# mapleCUx_large_4_1-018-not-produced.net
KiCad netlist of a schematic drawn in EAGLE
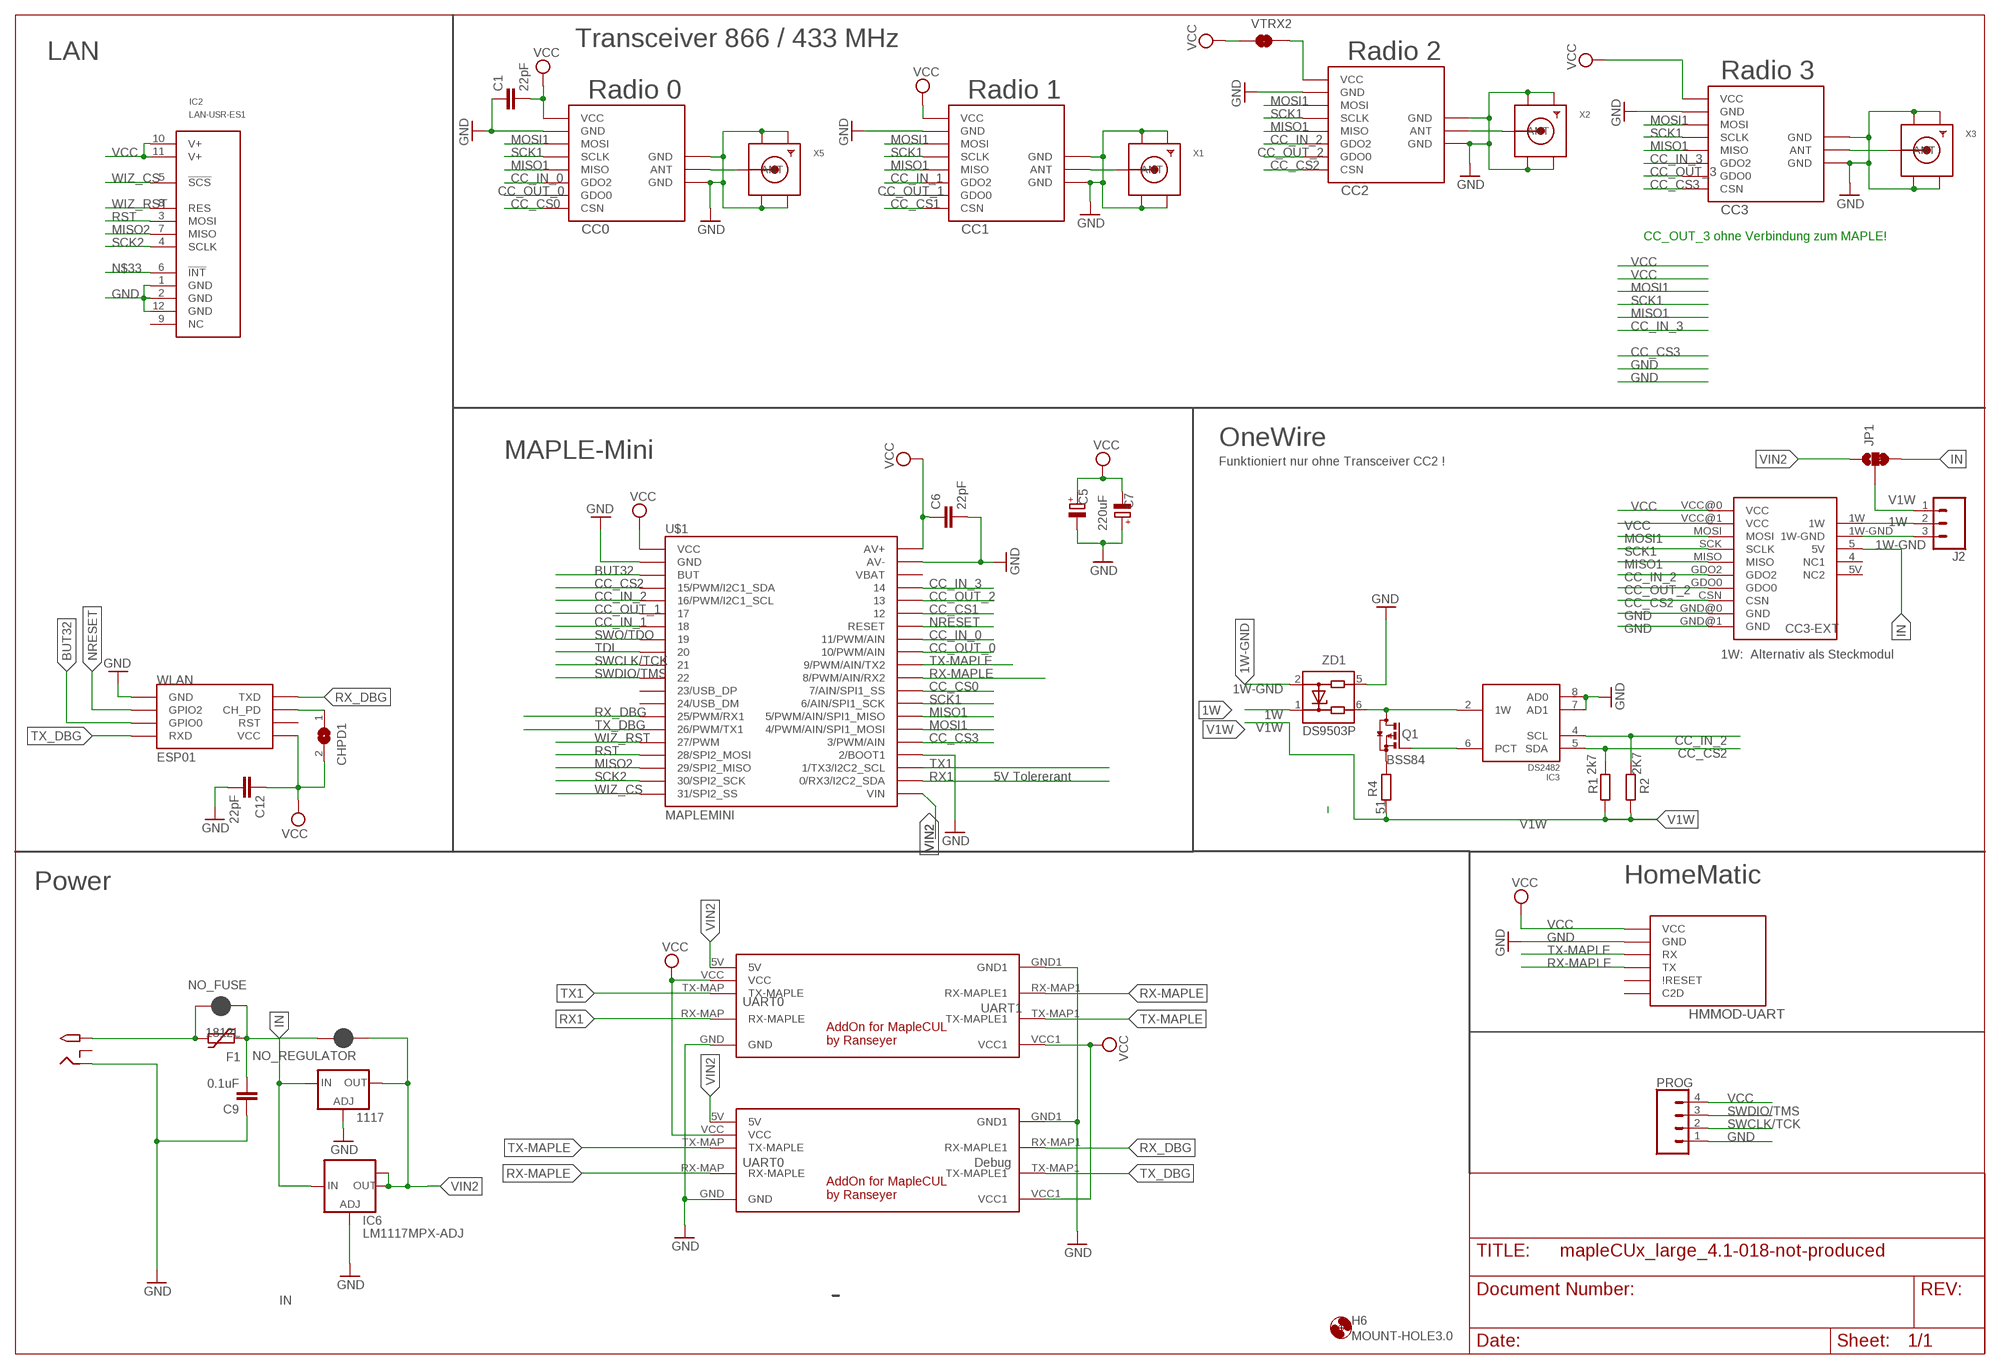
[diagram p0: schematic, sheet 1]

(export (version "E")
  (design (tool "Eeschema 10.0.6"))
  (components
    (comp (ref "1117")
      (value "LD117ADT50TR")
      (footprint "eagle-import:DPACK")
      (libsource (lib "eagle-import") (part "LD117A?DT50TR"))
    )
    (comp (ref "C1")
      (value "22pF")
      (footprint "eagle-import:C0805")
      (libsource (lib "eagle-import") (part "C-EUC0805"))
    )
    (comp (ref "C5")
      (value "220uF")
      (footprint "eagle-import:E5-8,5")
      (libsource (lib "eagle-import") (part "CPOL-EUE5-8.5"))
    )
    (comp (ref "C6")
      (value "22pF")
      (footprint "eagle-import:C0805")
      (libsource (lib "eagle-import") (part "C-EUC0805"))
    )
    (comp (ref "C7")
      (value "CPOL-EUSMCE")
      (footprint "eagle-import:SMC_E")
      (libsource (lib "eagle-import") (part "rcl_334_CPOL-EUSMCE"))
    )
    (comp (ref "C9")
      (value "0.1uF")
      (footprint "eagle-import:C1206")
      (libsource (lib "eagle-import") (part "C-EUC1206"))
    )
    (comp (ref "C12")
      (value "22pF")
      (footprint "eagle-import:C0805")
      (libsource (lib "eagle-import") (part "C-EUC0805"))
    )
    (comp (ref "CC0")
      (value "CC1101")
      (footprint "eagle-import:CC1101_MODULE1_SMD")
      (libsource (lib "eagle-import") (part "CC1101_MODULE1SMD"))
    )
    (comp (ref "CC1")
      (value "CC1101_MODULE1SMD")
      (footprint "eagle-import:CC1101_MODULE1_SMD")
      (libsource (lib "eagle-import") (part "CC1101_MODULE1SMD"))
    )
    (comp (ref "CC2")
      (value "CC1101_MODULE1SMD")
      (footprint "eagle-import:CC1101_MODULE1_SMD")
      (libsource (lib "eagle-import") (part "CC1101_MODULE1SMD"))
    )
    (comp (ref "CC3")
      (value "CC1101_MODULE1SMD")
      (footprint "eagle-import:CC1101_MODULE1_SMD")
      (libsource (lib "eagle-import") (part "CC1101_MODULE1SMD"))
    )
    (comp (ref "CC3-EXT")
      (value "ONEWIRE-MODULE")
      (footprint "eagle-import:ONEWIRE_CC1101_MODULE3_DIL")
      (libsource (lib "eagle-import") (part "ONEWIRE-MODULE"))
    )
    (comp (ref "CHPD1")
      (value "SJ")
      (footprint "eagle-import:SJ")
      (libsource (lib "eagle-import") (part "SJ"))
    )
    (comp (ref "F1")
      (value "1812L")
      (footprint "eagle-import:1812L")
      (libsource (lib "eagle-import") (part "1812L"))
    )
    (comp (ref "H6")
      (value "MOUNT-HOLE3.0")
      (footprint "eagle-import:3,0")
      (libsource (lib "eagle-import") (part "MOUNT-HOLE3.0"))
    )
    (comp (ref "HMMOD-UART")
      (value "HM-MOD-UARTDIL")
      (footprint "eagle-import:HM-MOD-UART-DIL")
      (libsource (lib "eagle-import") (part "HM-MOD-UARTDIL"))
    )
    (comp (ref "IC2")
      (value "LAN-USR-ES1")
      (footprint "eagle-import:USR-ES1")
      (libsource (lib "eagle-import") (part "LAN-USR-ES1"))
    )
    (comp (ref "IC3")
      (value "DS2482")
      (footprint "eagle-import:SO08")
      (libsource (lib "eagle-import") (part "DS2482-100S"))
    )
    (comp (ref "IC6")
      (value "LM1117MPX-ADJ")
      (footprint "eagle-import:SOT223")
      (libsource (lib "eagle-import") (part "LM1117MPX-ADJ"))
    )
    (comp (ref "J2")
      (value "CONN_03LONGPADS")
      (footprint "eagle-import:1X03_LONGPADS")
      (libsource (lib "eagle-import") (part "CONN_03LONGPADS"))
    )
    (comp (ref "JP1")
      (value "JUMPER-SMT_3_1-NC_TRACE_SILK")
      (footprint "eagle-import:SMT-JUMPER_3_1-NC_TRACE_SILK")
      (libsource (lib "eagle-import") (part "JUMPER-SMT_3_1-NC_TRACE_SILK"))
    )
    (comp (ref "NO_FUSE")
      (value "JUMPER-SMT_2_NC_PASTE_NO-SILK")
      (footprint "eagle-import:SMT-JUMPER_2_NC_PASTE_NO-SILK")
      (libsource (lib "eagle-import") (part "JUMPER-SMT_2_NC_PASTE_NO-SILK"))
    )
    (comp (ref "NO_REGULATOR")
      (value "JUMPER-SMT_2_NC_PASTE_NO-SILK")
      (footprint "eagle-import:SMT-JUMPER_2_NC_PASTE_NO-SILK")
      (libsource (lib "eagle-import") (part "JUMPER-SMT_2_NC_PASTE_NO-SILK"))
    )
    (comp (ref "PROG")
      (value "CONN_04LOCK")
      (footprint "eagle-import:1X04_LOCK")
      (libsource (lib "eagle-import") (part "CONN_04LOCK"))
    )
    (comp (ref "Q1")
      (value "BSS84")
      (footprint "eagle-import:SOT23")
      (libsource (lib "eagle-import") (part "BSS84"))
    )
    (comp (ref "R1")
      (value "2k7")
      (footprint "eagle-import:R0805")
      (libsource (lib "eagle-import") (part "R-EU_R0805"))
    )
    (comp (ref "R2")
      (value "2K7")
      (footprint "eagle-import:R0805")
      (libsource (lib "eagle-import") (part "R-EU_R0805"))
    )
    (comp (ref "R4")
      (value "51")
      (footprint "eagle-import:R0805")
      (libsource (lib "eagle-import") (part "R-EU_R0805"))
    )
    (comp (ref "U$1")
      (value "MAPLEMINI")
      (footprint "eagle-import:20-DIP")
      (libsource (lib "eagle-import") (part "MAPLEMINI"))
    )
    (comp (ref "U$2")
      (value "2.1MMJACKTHM")
      (footprint "eagle-import:PJ-102A")
      (libsource (lib "eagle-import") (part "2.1MMJACKTHM"))
    )
    (comp (ref "U$3")
      (value "MAPLE-CUL-ADDON-V01")
      (footprint "eagle-import:MAPLE-CUL-V01")
      (libsource (lib "eagle-import") (part "MAPLE-CUL-ADDON-V01"))
    )
    (comp (ref "U$4")
      (value "MAPLE-CUL-ADDON-V01")
      (footprint "eagle-import:MAPLE-CUL-V01")
      (libsource (lib "eagle-import") (part "MAPLE-CUL-ADDON-V01"))
    )
    (comp (ref "VTRX2")
      (value "JUMPER-SMT_2_NC_TRACE_SILK")
      (footprint "eagle-import:SMT-JUMPER_2_NC_TRACE_SILK")
      (libsource (lib "eagle-import") (part "JUMPER-SMT_2_NC_TRACE_SILK"))
    )
    (comp (ref "WLAN")
      (value "ESP01")
      (footprint "eagle-import:ESP01")
      (libsource (lib "eagle-import") (part "ESP01"))
    )
    (comp (ref "X1")
      (value "SMACONNECTOR_EDGE")
      (footprint "eagle-import:SMA_EDGELAUNCH")
      (libsource (lib "eagle-import") (part "SMACONNECTOR_EDGE"))
    )
    (comp (ref "X2")
      (value "SMACONNECTOR_EDGE")
      (footprint "eagle-import:SMA_EDGELAUNCH")
      (libsource (lib "eagle-import") (part "SMACONNECTOR_EDGE"))
    )
    (comp (ref "X3")
      (value "SMACONNECTOR_EDGE")
      (footprint "eagle-import:SMA_EDGELAUNCH")
      (libsource (lib "eagle-import") (part "SMACONNECTOR_EDGE"))
    )
    (comp (ref "X5")
      (value "SMACONNECTOR_EDGE")
      (footprint "eagle-import:SMA_EDGELAUNCH")
      (libsource (lib "eagle-import") (part "SMACONNECTOR_EDGE"))
    )
    (comp (ref "ZD1")
      (value "DS9503P")
      (footprint "eagle-import:TSOC6")
      (libsource (lib "eagle-import") (part "DS9503P"))
    )
  )
  (nets
    (net (code "1") (name "/CC_CS0") (class "Default")
      (node (ref "CC0") (pin "CSN") (pinfunction "CSN_CSN") (pintype "bidirectional"))
      (node (ref "U$1") (pin "29") (pinfunction "7/AIN/SPI1_SS_29") (pintype "bidirectional"))
    )
    (net (code "2") (name "/CC_CS1") (class "Default")
      (node (ref "CC1") (pin "CSN") (pinfunction "CSN_CSN") (pintype "bidirectional"))
      (node (ref "U$1") (pin "35") (pinfunction "12_35") (pintype "bidirectional"))
    )
    (net (code "3") (name "/CC_CS2") (class "Default")
      (node (ref "CC2") (pin "CSN") (pinfunction "CSN_CSN") (pintype "bidirectional"))
      (node (ref "CC3-EXT") (pin "CSN") (pinfunction "CSN_CSN") (pintype "bidirectional"))
      (node (ref "IC3") (pin "5") (pinfunction "SDA_5") (pintype "bidirectional"))
      (node (ref "R1") (pin "2") (pinfunction "2_2") (pintype "passive"))
      (node (ref "U$1") (pin "4") (pinfunction "15/PWM/I2C1_SDA_4") (pintype "bidirectional"))
    )
    (net (code "4") (name "/CC_CS3") (class "Default")
      (node (ref "CC3") (pin "CSN") (pinfunction "CSN_CSN") (pintype "bidirectional"))
      (node (ref "U$1") (pin "25") (pinfunction "3/PWM/AIN_25") (pintype "bidirectional"))
    )
    (net (code "5") (name "/CC_IN_0") (class "Default")
      (node (ref "CC0") (pin "GDO2") (pinfunction "GDO2_GDO2") (pintype "bidirectional"))
      (node (ref "U$1") (pin "33") (pinfunction "11/PWM/AIN_33") (pintype "bidirectional"))
    )
    (net (code "6") (name "/CC_IN_1") (class "Default")
      (node (ref "CC1") (pin "GDO2") (pinfunction "GDO2_GDO2") (pintype "bidirectional"))
      (node (ref "U$1") (pin "7") (pinfunction "18_7") (pintype "bidirectional"))
    )
    (net (code "7") (name "/CC_IN_2") (class "Default")
      (node (ref "CC2") (pin "GDO2") (pinfunction "GDO2_GDO2") (pintype "bidirectional"))
      (node (ref "CC3-EXT") (pin "GDO2") (pinfunction "GDO2_GDO2") (pintype "bidirectional"))
      (node (ref "IC3") (pin "4") (pinfunction "SCL_4") (pintype "input"))
      (node (ref "R2") (pin "2") (pinfunction "2_2") (pintype "passive"))
      (node (ref "U$1") (pin "5") (pinfunction "16/PWM/I2C1_SCL_5") (pintype "bidirectional"))
    )
    (net (code "8") (name "/CC_IN_3") (class "Default")
      (node (ref "CC3") (pin "GDO2") (pinfunction "GDO2_GDO2") (pintype "bidirectional"))
      (node (ref "U$1") (pin "37") (pinfunction "14_37") (pintype "bidirectional"))
    )
    (net (code "9") (name "/CC_OUT_0") (class "Default")
      (node (ref "CC0") (pin "GDO0") (pinfunction "GDO0_GDO0") (pintype "bidirectional"))
      (node (ref "U$1") (pin "32") (pinfunction "10/PWM/AIN_32") (pintype "bidirectional"))
    )
    (net (code "10") (name "/CC_OUT_1") (class "Default")
      (node (ref "CC1") (pin "GDO0") (pinfunction "GDO0_GDO0") (pintype "bidirectional"))
      (node (ref "U$1") (pin "6") (pinfunction "17_6") (pintype "bidirectional"))
    )
    (net (code "11") (name "/CC_OUT_2") (class "Default")
      (node (ref "CC2") (pin "GDO0") (pinfunction "GDO0_GDO0") (pintype "bidirectional"))
      (node (ref "CC3-EXT") (pin "GDO0") (pinfunction "GDO0_GDO0") (pintype "bidirectional"))
      (node (ref "U$1") (pin "36") (pinfunction "13_36") (pintype "bidirectional"))
    )
    (net (code "12") (name "/CC_OUT_3") (class "Default")
      (node (ref "CC3") (pin "GDO0") (pinfunction "GDO0_GDO0") (pintype "bidirectional"))
    )
    (net (code "13") (name "/MISO1") (class "Default")
      (node (ref "CC0") (pin "MISO") (pinfunction "MISO_MISO") (pintype "bidirectional"))
      (node (ref "CC1") (pin "MISO") (pinfunction "MISO_MISO") (pintype "bidirectional"))
      (node (ref "CC2") (pin "MISO") (pinfunction "MISO_MISO") (pintype "bidirectional"))
      (node (ref "CC3") (pin "MISO") (pinfunction "MISO_MISO") (pintype "bidirectional"))
      (node (ref "CC3-EXT") (pin "MISO") (pinfunction "MISO_MISO") (pintype "bidirectional"))
      (node (ref "U$1") (pin "27") (pinfunction "5/PWM/AIN/SPI1_MISO_27") (pintype "bidirectional"))
    )
    (net (code "14") (name "/MISO2") (class "Default")
      (node (ref "IC2") (pin "7") (pinfunction "MISO_7") (pintype "bidirectional"))
      (node (ref "U$1") (pin "18") (pinfunction "29/SPI2_MISO_18") (pintype "bidirectional"))
    )
    (net (code "15") (name "/MOSI1") (class "Default")
      (node (ref "CC0") (pin "MOSI") (pinfunction "MOSI_MOSI") (pintype "bidirectional"))
      (node (ref "CC1") (pin "MOSI") (pinfunction "MOSI_MOSI") (pintype "bidirectional"))
      (node (ref "CC2") (pin "MOSI") (pinfunction "MOSI_MOSI") (pintype "bidirectional"))
      (node (ref "CC3") (pin "MOSI") (pinfunction "MOSI_MOSI") (pintype "bidirectional"))
      (node (ref "CC3-EXT") (pin "MOSI") (pinfunction "MOSI_MOSI") (pintype "bidirectional"))
      (node (ref "U$1") (pin "26") (pinfunction "4/PWM/AIN/SPI1_MOSI_26") (pintype "bidirectional"))
    )
    (net (code "16") (name "/N$33") (class "Default")
      (node (ref "IC2") (pin "6") (pinfunction "~{INT}_6") (pintype "output"))
    )
    (net (code "17") (name "/RST") (class "Default")
      (node (ref "IC2") (pin "3") (pinfunction "MOSI_3") (pintype "bidirectional"))
      (node (ref "U$1") (pin "17") (pinfunction "28/SPI2_MOSI_17") (pintype "bidirectional"))
    )
    (net (code "18") (name "/SCK1") (class "Default")
      (node (ref "CC0") (pin "SCLK") (pinfunction "SCLK_SCLK") (pintype "bidirectional"))
      (node (ref "CC1") (pin "SCLK") (pinfunction "SCLK_SCLK") (pintype "bidirectional"))
      (node (ref "CC2") (pin "SCLK") (pinfunction "SCLK_SCLK") (pintype "bidirectional"))
      (node (ref "CC3") (pin "SCLK") (pinfunction "SCLK_SCLK") (pintype "bidirectional"))
      (node (ref "CC3-EXT") (pin "SCK") (pinfunction "SCLK_SCK") (pintype "bidirectional"))
      (node (ref "U$1") (pin "28") (pinfunction "6/AIN/SPI1_SCK_28") (pintype "bidirectional"))
    )
    (net (code "19") (name "/SCK2") (class "Default")
      (node (ref "IC2") (pin "4") (pinfunction "SCLK_4") (pintype "input"))
      (node (ref "U$1") (pin "19") (pinfunction "30/SPI2_SCK_19") (pintype "bidirectional"))
    )
    (net (code "20") (name "/SWCLK{slash}TCK") (class "Default")
      (node (ref "PROG") (pin "2") (pinfunction "2_2") (pintype "passive"))
      (node (ref "U$1") (pin "10") (pinfunction "21_10") (pintype "bidirectional"))
    )
    (net (code "21") (name "/SWDIO{slash}TMS") (class "Default")
      (node (ref "PROG") (pin "3") (pinfunction "3_3") (pintype "passive"))
      (node (ref "U$1") (pin "11") (pinfunction "22_11") (pintype "bidirectional"))
    )
    (net (code "22") (name "/SWO{slash}TDO") (class "Default")
      (node (ref "U$1") (pin "8") (pinfunction "19_8") (pintype "bidirectional"))
    )
    (net (code "23") (name "/TDI") (class "Default")
      (node (ref "U$1") (pin "9") (pinfunction "20_9") (pintype "bidirectional"))
    )
    (net (code "24") (name "/WIZ_CS") (class "Default")
      (node (ref "IC2") (pin "5") (pinfunction "~{SCS}_5") (pintype "input"))
      (node (ref "U$1") (pin "20") (pinfunction "31/SPI2_SS_20") (pintype "bidirectional"))
    )
    (net (code "25") (name "/WIZ_RST") (class "Default")
      (node (ref "IC2") (pin "8") (pinfunction "RES_8") (pintype "input"))
      (node (ref "U$1") (pin "16") (pinfunction "27/PWM_16") (pintype "bidirectional"))
    )
    (net (code "26") (name "1W") (class "Default")
      (node (ref "CC3-EXT") (pin "1W") (pinfunction "1W_1W") (pintype "bidirectional"))
      (node (ref "J2") (pin "2") (pinfunction "2_2") (pintype "passive"))
      (node (ref "ZD1") (pin "1") (pinfunction "P$1_1") (pintype "passive"))
    )
    (net (code "27") (name "1W-GND") (class "Default")
      (node (ref "CC3-EXT") (pin "1W-GND") (pinfunction "1W-GND_1W-GND") (pintype "bidirectional"))
      (node (ref "J2") (pin "3") (pinfunction "3_3") (pintype "passive"))
      (node (ref "ZD1") (pin "2") (pinfunction "P$2_2") (pintype "passive"))
    )
    (net (code "28") (name "BUT32") (class "Default")
      (node (ref "U$1") (pin "3") (pinfunction "BUT_3") (pintype "bidirectional"))
      (node (ref "WLAN") (pin "GPIO0") (pinfunction "GPIO0_GPIO0") (pintype "bidirectional"))
    )
    (net (code "29") (name "GND") (class "Default")
      (node (ref "1117") (pin "1") (pinfunction "ADJ_1") (pintype "input"))
      (node (ref "C1") (pin "1") (pinfunction "1_1") (pintype "passive"))
      (node (ref "C12") (pin "2") (pinfunction "2_2") (pintype "passive"))
      (node (ref "C5") (pin "-") (pinfunction "-_-") (pintype "passive"))
      (node (ref "C6") (pin "2") (pinfunction "2_2") (pintype "passive"))
      (node (ref "C7") (pin "+") (pinfunction "+_+") (pintype "passive"))
      (node (ref "C9") (pin "1") (pinfunction "1_1") (pintype "passive"))
      (node (ref "CC0") (pin "GND@0") (pinfunction "GND_GND@0") (pintype "power_in"))
      (node (ref "CC0") (pin "GND@1") (pinfunction "GND_GND@1") (pintype "power_in"))
      (node (ref "CC0") (pin "GND@2") (pinfunction "GND_GND@2") (pintype "power_in"))
      (node (ref "CC1") (pin "GND@0") (pinfunction "GND_GND@0") (pintype "power_in"))
      (node (ref "CC1") (pin "GND@1") (pinfunction "GND_GND@1") (pintype "power_in"))
      (node (ref "CC1") (pin "GND@2") (pinfunction "GND_GND@2") (pintype "power_in"))
      (node (ref "CC2") (pin "GND@0") (pinfunction "GND_GND@0") (pintype "power_in"))
      (node (ref "CC2") (pin "GND@1") (pinfunction "GND_GND@1") (pintype "power_in"))
      (node (ref "CC2") (pin "GND@2") (pinfunction "GND_GND@2") (pintype "power_in"))
      (node (ref "CC3") (pin "GND@0") (pinfunction "GND_GND@0") (pintype "power_in"))
      (node (ref "CC3") (pin "GND@1") (pinfunction "GND_GND@1") (pintype "power_in"))
      (node (ref "CC3") (pin "GND@2") (pinfunction "GND_GND@2") (pintype "power_in"))
      (node (ref "CC3-EXT") (pin "GND@0") (pinfunction "GND_GND@0") (pintype "power_in"))
      (node (ref "CC3-EXT") (pin "GND@1") (pinfunction "GND_GND@1") (pintype "power_in"))
      (node (ref "HMMOD-UART") (pin "2") (pinfunction "GND_2") (pintype "power_in"))
      (node (ref "IC2") (pin "1") (pinfunction "GND_1") (pintype "power_in"))
      (node (ref "IC2") (pin "12") (pinfunction "GND_12") (pintype "power_in"))
      (node (ref "IC2") (pin "2") (pinfunction "GND_2") (pintype "power_in"))
      (node (ref "IC3") (pin "7") (pinfunction "AD1_7") (pintype "input"))
      (node (ref "IC3") (pin "8") (pinfunction "AD0_8") (pintype "input"))
      (node (ref "IC6") (pin "1") (pinfunction "ADJ_1") (pintype "input"))
      (node (ref "PROG") (pin "1") (pinfunction "1_1") (pintype "passive"))
      (node (ref "U$1") (pin "2") (pinfunction "GND_2") (pintype "bidirectional"))
      (node (ref "U$1") (pin "24") (pinfunction "2/BOOT1_24") (pintype "bidirectional"))
      (node (ref "U$1") (pin "39") (pinfunction "AV-_39") (pintype "bidirectional"))
      (node (ref "U$2") (pin "RING") (pinfunction "RING_RING") (pintype "bidirectional"))
      (node (ref "U$3") (pin "GND") (pinfunction "GND_GND") (pintype "bidirectional"))
      (node (ref "U$3") (pin "GND1") (pinfunction "GND1_GND1") (pintype "bidirectional"))
      (node (ref "U$4") (pin "GND") (pinfunction "GND_GND") (pintype "bidirectional"))
      (node (ref "U$4") (pin "GND1") (pinfunction "GND1_GND1") (pintype "bidirectional"))
      (node (ref "WLAN") (pin "GND") (pinfunction "GND_GND") (pintype "bidirectional"))
      (node (ref "X1") (pin "GND@1") (pinfunction "GND4_GND@1") (pintype "power_in"))
      (node (ref "X1") (pin "GND@2") (pinfunction "GND3_GND@2") (pintype "power_in"))
      (node (ref "X1") (pin "GND@3") (pinfunction "GND2_GND@3") (pintype "power_in"))
      (node (ref "X1") (pin "GND@4") (pinfunction "GND1_GND@4") (pintype "power_in"))
      (node (ref "X2") (pin "GND@1") (pinfunction "GND4_GND@1") (pintype "power_in"))
      (node (ref "X2") (pin "GND@2") (pinfunction "GND3_GND@2") (pintype "power_in"))
      (node (ref "X2") (pin "GND@3") (pinfunction "GND2_GND@3") (pintype "power_in"))
      (node (ref "X2") (pin "GND@4") (pinfunction "GND1_GND@4") (pintype "power_in"))
      (node (ref "X3") (pin "GND@1") (pinfunction "GND4_GND@1") (pintype "power_in"))
      (node (ref "X3") (pin "GND@2") (pinfunction "GND3_GND@2") (pintype "power_in"))
      (node (ref "X3") (pin "GND@3") (pinfunction "GND2_GND@3") (pintype "power_in"))
      (node (ref "X3") (pin "GND@4") (pinfunction "GND1_GND@4") (pintype "power_in"))
      (node (ref "X5") (pin "GND@1") (pinfunction "GND4_GND@1") (pintype "power_in"))
      (node (ref "X5") (pin "GND@2") (pinfunction "GND3_GND@2") (pintype "power_in"))
      (node (ref "X5") (pin "GND@3") (pinfunction "GND2_GND@3") (pintype "power_in"))
      (node (ref "X5") (pin "GND@4") (pinfunction "GND1_GND@4") (pintype "power_in"))
      (node (ref "ZD1") (pin "5") (pinfunction "P$3_5") (pintype "passive"))
    )
    (net (code "30") (name "IN") (class "Default")
      (node (ref "1117") (pin "3") (pinfunction "IN_3") (pintype "input"))
      (node (ref "C9") (pin "2") (pinfunction "2_2") (pintype "passive"))
      (node (ref "CC3-EXT") (pin "5") (pinfunction "5V_5") (pintype "bidirectional"))
      (node (ref "F1") (pin "P$1") (pinfunction "1_P$1") (pintype "passive"))
      (node (ref "IC6") (pin "3") (pinfunction "IN_3") (pintype "input"))
      (node (ref "JP1") (pin "3") (pinfunction "3_3") (pintype "passive"))
      (node (ref "NO_FUSE") (pin "1") (pinfunction "1_1") (pintype "passive"))
      (node (ref "NO_REGULATOR") (pin "2") (pinfunction "2_2") (pintype "passive"))
    )
    (net (code "31") (name "NRESET") (class "Default")
      (node (ref "U$1") (pin "34") (pinfunction "RESET_34") (pintype "bidirectional"))
      (node (ref "WLAN") (pin "GPIO2") (pinfunction "GPIO2_GPIO2") (pintype "bidirectional"))
    )
    (net (code "32") (name "Net-(CC2-PadVCC)") (class "Default")
      (node (ref "CC2") (pin "VCC") (pinfunction "VCC_VCC") (pintype "power_in"))
      (node (ref "VTRX2") (pin "2") (pinfunction "2_2") (pintype "passive"))
    )
    (net (code "33") (name "Net-(CHPD1-Pad1)") (class "Default")
      (node (ref "CHPD1") (pin "1") (pinfunction "1_1") (pintype "passive"))
      (node (ref "WLAN") (pin "CH_PD") (pinfunction "CH_PD_CH_PD") (pintype "bidirectional"))
    )
    (net (code "34") (name "Net-(F1-2)") (class "Default")
      (node (ref "F1") (pin "P$2") (pinfunction "2_P$2") (pintype "passive"))
      (node (ref "NO_FUSE") (pin "2") (pinfunction "2_2") (pintype "passive"))
      (node (ref "U$2") (pin "TIP") (pinfunction "TIP_TIP") (pintype "bidirectional"))
    )
    (net (code "35") (name "Net-(IC3A-1W)") (class "Default")
      (node (ref "IC3") (pin "2") (pinfunction "1W_2") (pintype "open_collector"))
      (node (ref "Q1") (pin "3") (pinfunction "D_3") (pintype "passive"))
      (node (ref "ZD1") (pin "6") (pinfunction "P$4_6") (pintype "passive"))
    )
    (net (code "36") (name "Net-(IC3A-PCT)") (class "Default")
      (node (ref "IC3") (pin "6") (pinfunction "PCT_6") (pintype "output"))
      (node (ref "Q1") (pin "1") (pinfunction "G_1") (pintype "passive"))
    )
    (net (code "37") (name "Net-(Q1-S)") (class "Default")
      (node (ref "Q1") (pin "2") (pinfunction "S_2") (pintype "passive"))
      (node (ref "R4") (pin "1") (pinfunction "1_1") (pintype "passive"))
    )
    (net (code "38") (name "Net-(X1-ANT)") (class "Default")
      (node (ref "CC1") (pin "ANT") (pinfunction "ANT_ANT") (pintype "output"))
      (node (ref "X1") (pin "P") (pinfunction "ANT_P") (pintype "bidirectional"))
    )
    (net (code "39") (name "Net-(X2-ANT)") (class "Default")
      (node (ref "CC2") (pin "ANT") (pinfunction "ANT_ANT") (pintype "output"))
      (node (ref "X2") (pin "P") (pinfunction "ANT_P") (pintype "bidirectional"))
    )
    (net (code "40") (name "Net-(X3-ANT)") (class "Default")
      (node (ref "CC3") (pin "ANT") (pinfunction "ANT_ANT") (pintype "output"))
      (node (ref "X3") (pin "P") (pinfunction "ANT_P") (pintype "bidirectional"))
    )
    (net (code "41") (name "Net-(X5-ANT)") (class "Default")
      (node (ref "CC0") (pin "ANT") (pinfunction "ANT_ANT") (pintype "output"))
      (node (ref "X5") (pin "P") (pinfunction "ANT_P") (pintype "bidirectional"))
    )
    (net (code "42") (name "RX-MAPLE") (class "Default")
      (node (ref "HMMOD-UART") (pin "5") (pinfunction "TX_5") (pintype "bidirectional"))
      (node (ref "U$1") (pin "30") (pinfunction "8/PWM/AIN/RX2_30") (pintype "bidirectional"))
      (node (ref "U$3") (pin "RX-MAP1") (pinfunction "RX-MAPLE1_RX-MAP1") (pintype "bidirectional"))
      (node (ref "U$4") (pin "RX-MAP") (pinfunction "RX-MAPLE_RX-MAP") (pintype "bidirectional"))
    )
    (net (code "43") (name "RX1") (class "Default")
      (node (ref "U$1") (pin "22") (pinfunction "0/RX3/I2C2_SDA_22") (pintype "bidirectional"))
      (node (ref "U$3") (pin "RX-MAP") (pinfunction "RX-MAPLE_RX-MAP") (pintype "bidirectional"))
    )
    (net (code "44") (name "RX_DBG") (class "Default")
      (node (ref "U$1") (pin "14") (pinfunction "25/PWM/RX1_14") (pintype "bidirectional"))
      (node (ref "U$4") (pin "RX-MAP1") (pinfunction "RX-MAPLE1_RX-MAP1") (pintype "bidirectional"))
      (node (ref "WLAN") (pin "TX") (pinfunction "TXD_TX") (pintype "bidirectional"))
    )
    (net (code "45") (name "TX-MAPLE") (class "Default")
      (node (ref "HMMOD-UART") (pin "6") (pinfunction "RX_6") (pintype "bidirectional"))
      (node (ref "U$1") (pin "31") (pinfunction "9/PWM/AIN/TX2_31") (pintype "bidirectional"))
      (node (ref "U$3") (pin "TX-MAP1") (pinfunction "TX-MAPLE1_TX-MAP1") (pintype "bidirectional"))
      (node (ref "U$4") (pin "TX-MAP") (pinfunction "TX-MAPLE_TX-MAP") (pintype "bidirectional"))
    )
    (net (code "46") (name "TX1") (class "Default")
      (node (ref "U$1") (pin "23") (pinfunction "1/TX3/I2C2_SCL_23") (pintype "bidirectional"))
      (node (ref "U$3") (pin "TX-MAP") (pinfunction "TX-MAPLE_TX-MAP") (pintype "bidirectional"))
    )
    (net (code "47") (name "TX_DBG") (class "Default")
      (node (ref "U$1") (pin "15") (pinfunction "26/PWM/TX1_15") (pintype "bidirectional"))
      (node (ref "U$4") (pin "TX-MAP1") (pinfunction "TX-MAPLE1_TX-MAP1") (pintype "bidirectional"))
      (node (ref "WLAN") (pin "RX") (pinfunction "RXD_RX") (pintype "bidirectional"))
    )
    (net (code "48") (name "V1W") (class "Default")
      (node (ref "J2") (pin "1") (pinfunction "1_1") (pintype "passive"))
      (node (ref "JP1") (pin "2") (pinfunction "2_2") (pintype "passive"))
      (node (ref "R1") (pin "1") (pinfunction "1_1") (pintype "passive"))
      (node (ref "R2") (pin "1") (pinfunction "1_1") (pintype "passive"))
      (node (ref "R4") (pin "2") (pinfunction "2_2") (pintype "passive"))
    )
    (net (code "49") (name "VCC") (class "Default")
      (node (ref "C1") (pin "2") (pinfunction "2_2") (pintype "passive"))
      (node (ref "C12") (pin "1") (pinfunction "1_1") (pintype "passive"))
      (node (ref "C5") (pin "+") (pinfunction "+_+") (pintype "passive"))
      (node (ref "C6") (pin "1") (pinfunction "1_1") (pintype "passive"))
      (node (ref "C7") (pin "-") (pinfunction "-_-") (pintype "passive"))
      (node (ref "CC0") (pin "VCC") (pinfunction "VCC_VCC") (pintype "power_in"))
      (node (ref "CC1") (pin "VCC") (pinfunction "VCC_VCC") (pintype "power_in"))
      (node (ref "CC3") (pin "VCC") (pinfunction "VCC_VCC") (pintype "power_in"))
      (node (ref "CC3-EXT") (pin "VCC@0") (pinfunction "VCC_VCC@0") (pintype "power_in"))
      (node (ref "CC3-EXT") (pin "VCC@1") (pinfunction "VCC_VCC@1") (pintype "power_in"))
      (node (ref "CHPD1") (pin "2") (pinfunction "2_2") (pintype "passive"))
      (node (ref "HMMOD-UART") (pin "1") (pinfunction "VCC_1") (pintype "power_in"))
      (node (ref "IC2") (pin "10") (pinfunction "V+_10") (pintype "power_in"))
      (node (ref "IC2") (pin "11") (pinfunction "V+_11") (pintype "power_in"))
      (node (ref "PROG") (pin "4") (pinfunction "4_4") (pintype "passive"))
      (node (ref "U$1") (pin "1") (pinfunction "VCC_1") (pintype "bidirectional"))
      (node (ref "U$1") (pin "40") (pinfunction "AV+_40") (pintype "bidirectional"))
      (node (ref "U$3") (pin "VCC") (pinfunction "VCC_VCC") (pintype "bidirectional"))
      (node (ref "U$3") (pin "VCC1") (pinfunction "VCC1_VCC1") (pintype "bidirectional"))
      (node (ref "U$4") (pin "VCC") (pinfunction "VCC_VCC") (pintype "bidirectional"))
      (node (ref "U$4") (pin "VCC1") (pinfunction "VCC1_VCC1") (pintype "bidirectional"))
      (node (ref "VTRX2") (pin "1") (pinfunction "1_1") (pintype "passive"))
      (node (ref "WLAN") (pin "VCC") (pinfunction "VCC_VCC") (pintype "bidirectional"))
    )
    (net (code "50") (name "VIN2") (class "Default")
      (node (ref "1117") (pin "4") (pinfunction "OUT_4") (pintype "passive"))
      (node (ref "IC6") (pin "2") (pinfunction "OUT_2") (pintype "passive"))
      (node (ref "IC6") (pin "TAB") (pinfunction "OUT1_TAB") (pintype "passive"))
      (node (ref "JP1") (pin "1") (pinfunction "1_1") (pintype "passive"))
      (node (ref "NO_REGULATOR") (pin "1") (pinfunction "1_1") (pintype "passive"))
      (node (ref "U$1") (pin "21") (pinfunction "VIN_21") (pintype "bidirectional"))
      (node (ref "U$3") (pin "5V") (pinfunction "5V_5V") (pintype "bidirectional"))
      (node (ref "U$4") (pin "5V") (pinfunction "5V_5V") (pintype "bidirectional"))
    )
    (net (code "51") (name "unconnected-(CC3-EXT-NC1-Pad4)") (class "Default")
      (node (ref "CC3-EXT") (pin "4") (pinfunction "NC1_4") (pintype "bidirectional"))
    )
    (net (code "52") (name "unconnected-(CC3-EXT-NC2-Pad5V)") (class "Default")
      (node (ref "CC3-EXT") (pin "5V") (pinfunction "NC2_5V") (pintype "bidirectional"))
    )
    (net (code "53") (name "unconnected-(HMMOD-UART-C2D-Pad3)") (class "Default")
      (node (ref "HMMOD-UART") (pin "3") (pinfunction "C2D_3") (pintype "bidirectional"))
    )
    (net (code "54") (name "unconnected-(HMMOD-UART-\\~{RESET}-Pad4)") (class "Default")
      (node (ref "HMMOD-UART") (pin "4") (pinfunction "\\~{RESET}_4") (pintype "bidirectional"))
    )
    (net (code "55") (name "unconnected-(IC2-NC-Pad9)") (class "Default")
      (node (ref "IC2") (pin "9") (pinfunction "NC_9") (pintype "no_connect"))
    )
    (net (code "56") (name "unconnected-(U$1-23{slash}USB_DP-Pad12)") (class "Default")
      (node (ref "U$1") (pin "12") (pinfunction "23/USB_DP_12") (pintype "bidirectional"))
    )
    (net (code "57") (name "unconnected-(U$1-24{slash}USB_DM-Pad13)") (class "Default")
      (node (ref "U$1") (pin "13") (pinfunction "24/USB_DM_13") (pintype "bidirectional"))
    )
    (net (code "58") (name "unconnected-(U$1-VBAT-Pad38)") (class "Default")
      (node (ref "U$1") (pin "38") (pinfunction "VBAT_38") (pintype "bidirectional"))
    )
    (net (code "59") (name "unconnected-(U$2-PadRING_SW)") (class "Default")
      (node (ref "U$2") (pin "RING_SW") (pinfunction "RING_SW_RING_SW") (pintype "bidirectional"))
    )
    (net (code "60") (name "unconnected-(WLAN-PadRST)") (class "Default")
      (node (ref "WLAN") (pin "RST") (pinfunction "RST_RST") (pintype "bidirectional"))
    )
  )
)
